# SSBDemod.net
KiCad netlist of a schematic drawn in Altium Designer
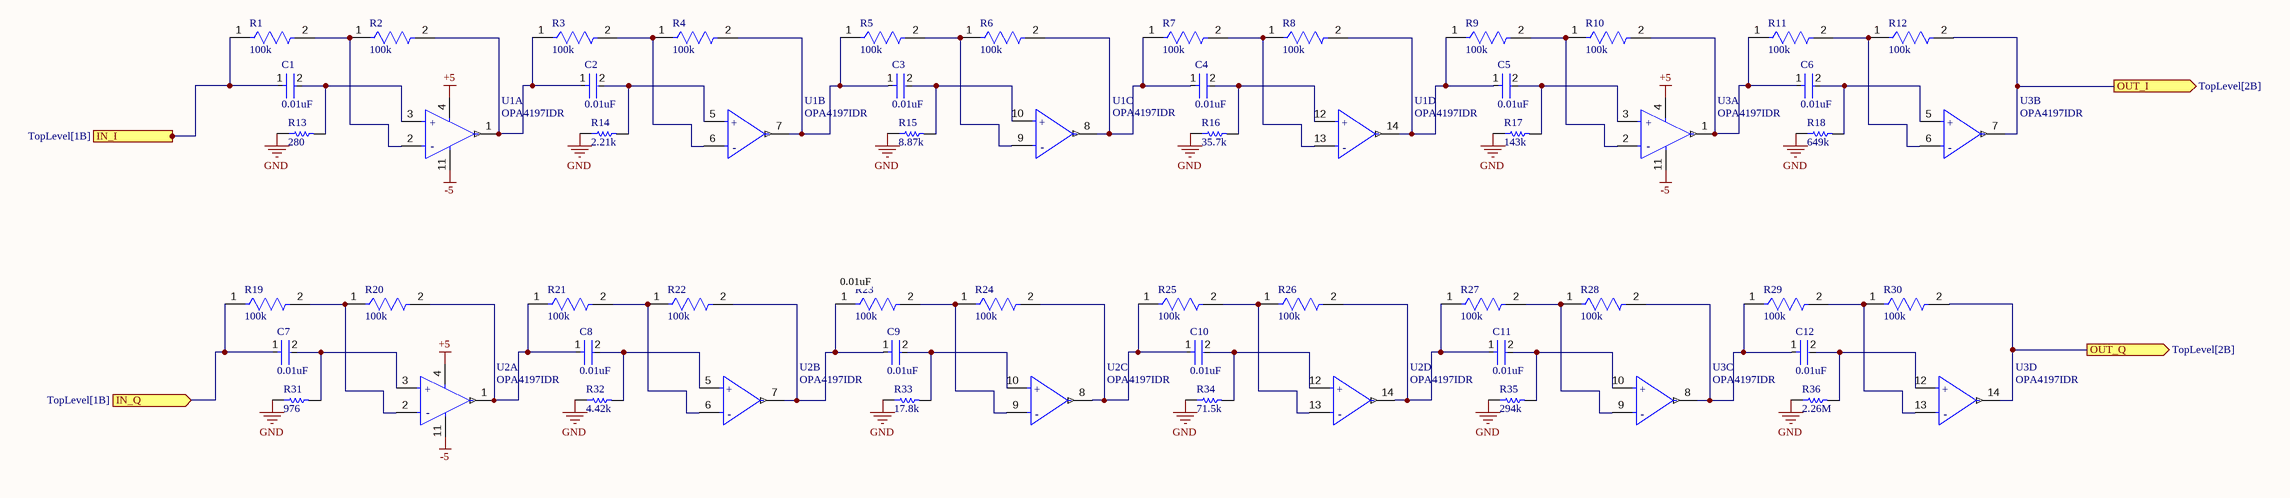
[diagram p0: SSBDemod.SchDoc]

(export (version "E")
  (design (tool "Eeschema 10.0.6"))
  (components
    (comp (ref "C1")
      (value "0.01uF")
      (footprint "FP-C0603C-CF-MFG")
      (description "CAP CER 10000PF 25V 1% NP0 0603")
      (fields
        (field (name "MANUFACTURER") "KEMET")
        (field (name "OCTOPART") "https://octopart.com/c0603c103f3gactu-kemet-12577573")
      )
      (libsource (lib "Altium Content Vault") (part "b4654b650e69147ec39a6b967a45e02"))
    )
    (comp (ref "C2")
      (value "0.01uF")
      (footprint "FP-C0603C-CF-MFG")
      (description "CAP CER 10000PF 25V 1% NP0 0603")
      (fields
        (field (name "MANUFACTURER") "KEMET")
        (field (name "OCTOPART") "https://octopart.com/c0603c103f3gactu-kemet-12577573")
      )
      (libsource (lib "Altium Content Vault") (part "b4654b650e69147ec39a6b967a45e02"))
    )
    (comp (ref "C3")
      (value "0.01uF")
      (footprint "FP-C0603C-CF-MFG")
      (description "CAP CER 10000PF 25V 1% NP0 0603")
      (fields
        (field (name "MANUFACTURER") "KEMET")
        (field (name "OCTOPART") "https://octopart.com/c0603c103f3gactu-kemet-12577573")
      )
      (libsource (lib "Altium Content Vault") (part "b4654b650e69147ec39a6b967a45e02"))
    )
    (comp (ref "C4")
      (value "0.01uF")
      (footprint "FP-C0603C-CF-MFG")
      (description "CAP CER 10000PF 25V 1% NP0 0603")
      (fields
        (field (name "MANUFACTURER") "KEMET")
        (field (name "OCTOPART") "https://octopart.com/c0603c103f3gactu-kemet-12577573")
      )
      (libsource (lib "Altium Content Vault") (part "b4654b650e69147ec39a6b967a45e02"))
    )
    (comp (ref "C5")
      (value "0.01uF")
      (footprint "FP-C0603C-CF-MFG")
      (description "CAP CER 10000PF 25V 1% NP0 0603")
      (fields
        (field (name "MANUFACTURER") "KEMET")
        (field (name "OCTOPART") "https://octopart.com/c0603c103f3gactu-kemet-12577573")
      )
      (libsource (lib "Altium Content Vault") (part "b4654b650e69147ec39a6b967a45e02"))
    )
    (comp (ref "C6")
      (value "0.01uF")
      (footprint "FP-C0603C-CF-MFG")
      (description "CAP CER 10000PF 25V 1% NP0 0603")
      (fields
        (field (name "MANUFACTURER") "KEMET")
        (field (name "OCTOPART") "https://octopart.com/c0603c103f3gactu-kemet-12577573")
      )
      (libsource (lib "Altium Content Vault") (part "b4654b650e69147ec39a6b967a45e02"))
    )
    (comp (ref "C7")
      (value "0.01uF")
      (footprint "FP-C0603C-CF-MFG")
      (description "CAP CER 10000PF 25V 1% NP0 0603")
      (fields
        (field (name "MANUFACTURER") "KEMET")
        (field (name "OCTOPART") "https://octopart.com/c0603c103f3gactu-kemet-12577573")
      )
      (libsource (lib "Altium Content Vault") (part "b4654b650e69147ec39a6b967a45e02"))
    )
    (comp (ref "C8")
      (value "0.01uF")
      (footprint "FP-C0603C-CF-MFG")
      (description "CAP CER 10000PF 25V 1% NP0 0603")
      (fields
        (field (name "MANUFACTURER") "KEMET")
        (field (name "OCTOPART") "https://octopart.com/c0603c103f3gactu-kemet-12577573")
      )
      (libsource (lib "Altium Content Vault") (part "b4654b650e69147ec39a6b967a45e02"))
    )
    (comp (ref "C9")
      (value "0.01uF")
      (footprint "FP-C0603C-CF-MFG")
      (description "CAP CER 10000PF 25V 1% NP0 0603")
      (fields
        (field (name "MANUFACTURER") "KEMET")
        (field (name "OCTOPART") "https://octopart.com/c0603c103f3gactu-kemet-12577573")
      )
      (libsource (lib "Altium Content Vault") (part "b4654b650e69147ec39a6b967a45e02"))
    )
    (comp (ref "C10")
      (value "0.01uF")
      (footprint "FP-C0603C-CF-MFG")
      (description "CAP CER 10000PF 25V 1% NP0 0603")
      (fields
        (field (name "MANUFACTURER") "KEMET")
        (field (name "OCTOPART") "https://octopart.com/c0603c103f3gactu-kemet-12577573")
      )
      (libsource (lib "Altium Content Vault") (part "b4654b650e69147ec39a6b967a45e02"))
    )
    (comp (ref "C11")
      (value "0.01uF")
      (footprint "FP-C0603C-CF-MFG")
      (description "CAP CER 10000PF 25V 1% NP0 0603")
      (fields
        (field (name "MANUFACTURER") "KEMET")
        (field (name "OCTOPART") "https://octopart.com/c0603c103f3gactu-kemet-12577573")
      )
      (libsource (lib "Altium Content Vault") (part "b4654b650e69147ec39a6b967a45e02"))
    )
    (comp (ref "C12")
      (value "0.01uF")
      (footprint "FP-C0603C-CF-MFG")
      (description "CAP CER 10000PF 25V 1% NP0 0603")
      (fields
        (field (name "MANUFACTURER") "KEMET")
        (field (name "OCTOPART") "https://octopart.com/c0603c103f3gactu-kemet-12577573")
      )
      (libsource (lib "Altium Content Vault") (part "b4654b650e69147ec39a6b967a45e02"))
    )
    (comp (ref "R1")
      (value "100k")
      (footprint "FP-RC0805-0_6-IPC_C")
      (description "RES 100K OHM 1% 1/8W 0805")
      (fields (field (name "TOLERANCE") "1%"))
      (libsource (lib "Altium Content Vault") (part "1029c3af85768c4190bb7ad29bc67b5"))
    )
    (comp (ref "R2")
      (value "100k")
      (footprint "FP-RC0805-0_6-IPC_C")
      (description "RES 100K OHM 1% 1/8W 0805")
      (fields (field (name "TOLERANCE") "1%"))
      (libsource (lib "Altium Content Vault") (part "1029c3af85768c4190bb7ad29bc67b5"))
    )
    (comp (ref "R3")
      (value "100k")
      (footprint "FP-RC0805-0_6-IPC_C")
      (description "RES 100K OHM 1% 1/8W 0805")
      (fields (field (name "TOLERANCE") "1%"))
      (libsource (lib "Altium Content Vault") (part "1029c3af85768c4190bb7ad29bc67b5"))
    )
    (comp (ref "R4")
      (value "100k")
      (footprint "FP-RC0805-0_6-IPC_C")
      (description "RES 100K OHM 1% 1/8W 0805")
      (fields (field (name "TOLERANCE") "1%"))
      (libsource (lib "Altium Content Vault") (part "1029c3af85768c4190bb7ad29bc67b5"))
    )
    (comp (ref "R5")
      (value "100k")
      (footprint "FP-RC0805-0_6-IPC_C")
      (description "RES 100K OHM 1% 1/8W 0805")
      (fields (field (name "TOLERANCE") "1%"))
      (libsource (lib "Altium Content Vault") (part "1029c3af85768c4190bb7ad29bc67b5"))
    )
    (comp (ref "R6")
      (value "100k")
      (footprint "FP-RC0805-0_6-IPC_C")
      (description "RES 100K OHM 1% 1/8W 0805")
      (fields (field (name "TOLERANCE") "1%"))
      (libsource (lib "Altium Content Vault") (part "1029c3af85768c4190bb7ad29bc67b5"))
    )
    (comp (ref "R7")
      (value "100k")
      (footprint "FP-RC0805-0_6-IPC_C")
      (description "RES 100K OHM 1% 1/8W 0805")
      (fields (field (name "TOLERANCE") "1%"))
      (libsource (lib "Altium Content Vault") (part "1029c3af85768c4190bb7ad29bc67b5"))
    )
    (comp (ref "R8")
      (value "100k")
      (footprint "FP-RC0805-0_6-IPC_C")
      (description "RES 100K OHM 1% 1/8W 0805")
      (fields (field (name "TOLERANCE") "1%"))
      (libsource (lib "Altium Content Vault") (part "1029c3af85768c4190bb7ad29bc67b5"))
    )
    (comp (ref "R9")
      (value "100k")
      (footprint "FP-RC0805-0_6-IPC_C")
      (description "RES 100K OHM 1% 1/8W 0805")
      (fields (field (name "TOLERANCE") "1%"))
      (libsource (lib "Altium Content Vault") (part "1029c3af85768c4190bb7ad29bc67b5"))
    )
    (comp (ref "R10")
      (value "100k")
      (footprint "FP-RC0805-0_6-IPC_C")
      (description "RES 100K OHM 1% 1/8W 0805")
      (fields (field (name "TOLERANCE") "1%"))
      (libsource (lib "Altium Content Vault") (part "1029c3af85768c4190bb7ad29bc67b5"))
    )
    (comp (ref "R11")
      (value "100k")
      (footprint "FP-RC0805-0_6-IPC_C")
      (description "RES 100K OHM 1% 1/8W 0805")
      (fields (field (name "TOLERANCE") "1%"))
      (libsource (lib "Altium Content Vault") (part "1029c3af85768c4190bb7ad29bc67b5"))
    )
    (comp (ref "R12")
      (value "100k")
      (footprint "FP-RC0805-0_6-IPC_C")
      (description "RES 100K OHM 1% 1/8W 0805")
      (fields (field (name "TOLERANCE") "1%"))
      (libsource (lib "Altium Content Vault") (part "1029c3af85768c4190bb7ad29bc67b5"))
    )
    (comp (ref "R13")
      (value "280")
      (footprint "RESC2013X60X35ML10T20")
      (fields (field (name "MANUFACTURER") "Yageo") (field (name "PART NUMBER") "RC0805FR-07280RL"))
      (libsource (lib "Altium Content Vault") (part "RES"))
    )
    (comp (ref "R14")
      (value "2.21k")
      (footprint "RESC2013X60X35ML10T20")
      (fields (field (name "MANUFACTURER") "Yageo") (field (name "PART NUMBER") "RC0805FR-072K21L"))
      (libsource (lib "Altium Content Vault") (part "RES"))
    )
    (comp (ref "R15")
      (value "8.87k")
      (footprint "RESC2013X60X35ML10T20")
      (fields (field (name "MANUFACTURER") "Yageo") (field (name "PART NUMBER") "RC0805FR-07280RL"))
      (libsource (lib "Altium Content Vault") (part "RES"))
    )
    (comp (ref "R16")
      (value "35.7k")
      (footprint "RESC2013X60X35ML10T20")
      (fields (field (name "MANUFACTURER") "Yageo") (field (name "PART NUMBER") "RC0805FR-07280RL"))
      (libsource (lib "Altium Content Vault") (part "RES"))
    )
    (comp (ref "R17")
      (value "143k")
      (footprint "RESC2013X60X35ML10T20")
      (fields (field (name "MANUFACTURER") "Yageo") (field (name "PART NUMBER") "RC0805FR-07280RL"))
      (libsource (lib "Altium Content Vault") (part "RES"))
    )
    (comp (ref "R18")
      (value "649k")
      (footprint "RESC2013X60X35ML10T20")
      (fields (field (name "MANUFACTURER") "Yageo") (field (name "PART NUMBER") "RC0805FR-07280RL"))
      (libsource (lib "Altium Content Vault") (part "RES"))
    )
    (comp (ref "R19")
      (value "100k")
      (footprint "FP-RC0805-0_6-IPC_C")
      (description "RES 100K OHM 1% 1/8W 0805")
      (fields (field (name "TOLERANCE") "1%"))
      (libsource (lib "Altium Content Vault") (part "1029c3af85768c4190bb7ad29bc67b5"))
    )
    (comp (ref "R20")
      (value "100k")
      (footprint "FP-RC0805-0_6-IPC_C")
      (description "RES 100K OHM 1% 1/8W 0805")
      (fields (field (name "TOLERANCE") "1%"))
      (libsource (lib "Altium Content Vault") (part "1029c3af85768c4190bb7ad29bc67b5"))
    )
    (comp (ref "R21")
      (value "100k")
      (footprint "FP-RC0805-0_6-IPC_C")
      (description "RES 100K OHM 1% 1/8W 0805")
      (fields (field (name "TOLERANCE") "1%"))
      (libsource (lib "Altium Content Vault") (part "1029c3af85768c4190bb7ad29bc67b5"))
    )
    (comp (ref "R22")
      (value "100k")
      (footprint "FP-RC0805-0_6-IPC_C")
      (description "RES 100K OHM 1% 1/8W 0805")
      (fields (field (name "TOLERANCE") "1%"))
      (libsource (lib "Altium Content Vault") (part "1029c3af85768c4190bb7ad29bc67b5"))
    )
    (comp (ref "R23")
      (value "100k")
      (footprint "FP-RC0805-0_6-IPC_C")
      (description "RES 100K OHM 1% 1/8W 0805")
      (fields (field (name "TOLERANCE") "1%"))
      (libsource (lib "Altium Content Vault") (part "1029c3af85768c4190bb7ad29bc67b5"))
    )
    (comp (ref "R24")
      (value "100k")
      (footprint "FP-RC0805-0_6-IPC_C")
      (description "RES 100K OHM 1% 1/8W 0805")
      (fields (field (name "TOLERANCE") "1%"))
      (libsource (lib "Altium Content Vault") (part "1029c3af85768c4190bb7ad29bc67b5"))
    )
    (comp (ref "R25")
      (value "100k")
      (footprint "FP-RC0805-0_6-IPC_C")
      (description "RES 100K OHM 1% 1/8W 0805")
      (fields (field (name "TOLERANCE") "1%"))
      (libsource (lib "Altium Content Vault") (part "1029c3af85768c4190bb7ad29bc67b5"))
    )
    (comp (ref "R26")
      (value "100k")
      (footprint "FP-RC0805-0_6-IPC_C")
      (description "RES 100K OHM 1% 1/8W 0805")
      (fields (field (name "TOLERANCE") "1%"))
      (libsource (lib "Altium Content Vault") (part "1029c3af85768c4190bb7ad29bc67b5"))
    )
    (comp (ref "R27")
      (value "100k")
      (footprint "FP-RC0805-0_6-IPC_C")
      (description "RES 100K OHM 1% 1/8W 0805")
      (fields (field (name "TOLERANCE") "1%"))
      (libsource (lib "Altium Content Vault") (part "1029c3af85768c4190bb7ad29bc67b5"))
    )
    (comp (ref "R28")
      (value "100k")
      (footprint "FP-RC0805-0_6-IPC_C")
      (description "RES 100K OHM 1% 1/8W 0805")
      (fields (field (name "TOLERANCE") "1%"))
      (libsource (lib "Altium Content Vault") (part "1029c3af85768c4190bb7ad29bc67b5"))
    )
    (comp (ref "R29")
      (value "100k")
      (footprint "FP-RC0805-0_6-IPC_C")
      (description "RES 100K OHM 1% 1/8W 0805")
      (fields (field (name "TOLERANCE") "1%"))
      (libsource (lib "Altium Content Vault") (part "1029c3af85768c4190bb7ad29bc67b5"))
    )
    (comp (ref "R30")
      (value "100k")
      (footprint "FP-RC0805-0_6-IPC_C")
      (description "RES 100K OHM 1% 1/8W 0805")
      (fields (field (name "TOLERANCE") "1%"))
      (libsource (lib "Altium Content Vault") (part "1029c3af85768c4190bb7ad29bc67b5"))
    )
    (comp (ref "R31")
      (value "976")
      (footprint "RESC2013X60X35ML10T20")
      (fields (field (name "MANUFACTURER") "Yageo") (field (name "PART NUMBER") "RC0805FR-07280RL"))
      (libsource (lib "Altium Content Vault") (part "RES"))
    )
    (comp (ref "R32")
      (value "4.42k")
      (footprint "RESC2013X60X35ML10T20")
      (fields (field (name "MANUFACTURER") "Yageo") (field (name "PART NUMBER") "RC0805FR-07280RL"))
      (libsource (lib "Altium Content Vault") (part "RES"))
    )
    (comp (ref "R33")
      (value "17.8k")
      (footprint "RESC2013X60X35ML10T20")
      (fields (field (name "MANUFACTURER") "Yageo") (field (name "PART NUMBER") "RC0805FR-07280RL"))
      (libsource (lib "Altium Content Vault") (part "RES"))
    )
    (comp (ref "R34")
      (value "71.5k")
      (footprint "RESC2013X60X35ML10T20")
      (fields (field (name "MANUFACTURER") "Yageo") (field (name "PART NUMBER") "RC0805FR-07280RL"))
      (libsource (lib "Altium Content Vault") (part "RES"))
    )
    (comp (ref "R35")
      (value "294k")
      (footprint "RESC2013X60X35ML10T20")
      (fields (field (name "MANUFACTURER") "Yageo") (field (name "PART NUMBER") "RC0805FR-07280RL"))
      (libsource (lib "Altium Content Vault") (part "RES"))
    )
    (comp (ref "R36")
      (value "2.26M")
      (footprint "RESC2013X60X35ML10T20")
      (fields (field (name "MANUFACTURER") "Yageo") (field (name "PART NUMBER") "RC0805FR-07280RL"))
      (libsource (lib "Altium Content Vault") (part "RES"))
    )
    (comp (ref "U1")
      (value "OPA4197IDR")
      (footprint "FP-D0014A-MFG")
      (description "IC OPAMP GP 4 CIRCUIT 14SOIC")
      (libsource (lib "Altium Content Vault") (part "684fa0f315d4229452f837ea2b10642"))
    )
    (comp (ref "U2")
      (value "OPA4197IDR")
      (footprint "FP-D0014A-MFG")
      (description "IC OPAMP GP 4 CIRCUIT 14SOIC")
      (libsource (lib "Altium Content Vault") (part "684fa0f315d4229452f837ea2b10642"))
    )
    (comp (ref "U3")
      (value "OPA4197IDR")
      (footprint "FP-D0014A-MFG")
      (description "IC OPAMP GP 4 CIRCUIT 14SOIC")
      (libsource (lib "Altium Content Vault") (part "684fa0f315d4229452f837ea2b10642"))
    )
  )
  (nets
    (net (code "1") (name "+5") (class "Default")
      (node (ref "U1") (pin "4") (pinfunction "V+_4") (pintype "power_in"))
      (node (ref "U2") (pin "4") (pinfunction "V+_4") (pintype "power_in"))
      (node (ref "U3") (pin "4") (pinfunction "V+_4") (pintype "power_in"))
    )
    (net (code "2") (name "-5") (class "Default")
      (node (ref "U1") (pin "11") (pinfunction "V-_11") (pintype "power_in"))
      (node (ref "U2") (pin "11") (pinfunction "V-_11") (pintype "power_in"))
      (node (ref "U3") (pin "11") (pinfunction "V-_11") (pintype "power_in"))
    )
    (net (code "3") (name "/IN_I") (class "Default")
      (node (ref "C1") (pin "1") (pinfunction "1_1") (pintype "passive"))
      (node (ref "R1") (pin "1") (pinfunction "1_1") (pintype "passive"))
    )
    (net (code "4") (name "/IN_Q") (class "Default")
      (node (ref "C7") (pin "1") (pinfunction "1_1") (pintype "passive"))
      (node (ref "R19") (pin "1") (pinfunction "1_1") (pintype "passive"))
    )
    (net (code "5") (name "/OUT_I") (class "Default")
      (node (ref "R12") (pin "2") (pinfunction "2_2") (pintype "passive"))
      (node (ref "U3") (pin "7") (pinfunction "OUT_B_7") (pintype "output"))
    )
    (net (code "6") (name "/OUT_Q") (class "Default")
      (node (ref "R30") (pin "2") (pinfunction "2_2") (pintype "passive"))
      (node (ref "U3") (pin "14") (pinfunction "OUT_D_14") (pintype "output"))
    )
    (net (code "7") (name "GND") (class "Default")
      (node (ref "R13") (pin "1") (pinfunction "1_1") (pintype "passive"))
      (node (ref "R14") (pin "1") (pinfunction "1_1") (pintype "passive"))
      (node (ref "R15") (pin "1") (pinfunction "1_1") (pintype "passive"))
      (node (ref "R16") (pin "1") (pinfunction "1_1") (pintype "passive"))
      (node (ref "R17") (pin "1") (pinfunction "1_1") (pintype "passive"))
      (node (ref "R18") (pin "1") (pinfunction "1_1") (pintype "passive"))
      (node (ref "R31") (pin "1") (pinfunction "1_1") (pintype "passive"))
      (node (ref "R32") (pin "1") (pinfunction "1_1") (pintype "passive"))
      (node (ref "R33") (pin "1") (pinfunction "1_1") (pintype "passive"))
      (node (ref "R34") (pin "1") (pinfunction "1_1") (pintype "passive"))
      (node (ref "R35") (pin "1") (pinfunction "1_1") (pintype "passive"))
      (node (ref "R36") (pin "1") (pinfunction "1_1") (pintype "passive"))
    )
    (net (code "8") (name "Net-(U1A-+IN_A)") (class "Default")
      (node (ref "C1") (pin "2") (pinfunction "2_2") (pintype "passive"))
      (node (ref "R13") (pin "2") (pinfunction "2_2") (pintype "passive"))
      (node (ref "U1") (pin "3") (pinfunction "+IN_A_3") (pintype "tri_state"))
    )
    (net (code "9") (name "Net-(U1A--IN_A)") (class "Default")
      (node (ref "R1") (pin "2") (pinfunction "2_2") (pintype "passive"))
      (node (ref "R2") (pin "1") (pinfunction "1_1") (pintype "passive"))
      (node (ref "U1") (pin "2") (pinfunction "-IN_A_2") (pintype "tri_state"))
    )
    (net (code "10") (name "Net-(U1A-OUT_A)") (class "Default")
      (node (ref "C2") (pin "1") (pinfunction "1_1") (pintype "passive"))
      (node (ref "R2") (pin "2") (pinfunction "2_2") (pintype "passive"))
      (node (ref "R3") (pin "1") (pinfunction "1_1") (pintype "passive"))
      (node (ref "U1") (pin "1") (pinfunction "OUT_A_1") (pintype "output"))
    )
    (net (code "11") (name "Net-(U1B-+IN_B)") (class "Default")
      (node (ref "C2") (pin "2") (pinfunction "2_2") (pintype "passive"))
      (node (ref "R14") (pin "2") (pinfunction "2_2") (pintype "passive"))
      (node (ref "U1") (pin "5") (pinfunction "+IN_B_5") (pintype "tri_state"))
    )
    (net (code "12") (name "Net-(U1B--IN_B)") (class "Default")
      (node (ref "R3") (pin "2") (pinfunction "2_2") (pintype "passive"))
      (node (ref "R4") (pin "1") (pinfunction "1_1") (pintype "passive"))
      (node (ref "U1") (pin "6") (pinfunction "-IN_B_6") (pintype "tri_state"))
    )
    (net (code "13") (name "Net-(U1B-OUT_B)") (class "Default")
      (node (ref "C3") (pin "1") (pinfunction "1_1") (pintype "passive"))
      (node (ref "R4") (pin "2") (pinfunction "2_2") (pintype "passive"))
      (node (ref "R5") (pin "1") (pinfunction "1_1") (pintype "passive"))
      (node (ref "U1") (pin "7") (pinfunction "OUT_B_7") (pintype "output"))
    )
    (net (code "14") (name "Net-(U1C-+IN_C)") (class "Default")
      (node (ref "C3") (pin "2") (pinfunction "2_2") (pintype "passive"))
      (node (ref "R15") (pin "2") (pinfunction "2_2") (pintype "passive"))
      (node (ref "U1") (pin "10") (pinfunction "+IN_C_10") (pintype "tri_state"))
    )
    (net (code "15") (name "Net-(U1C--IN_C)") (class "Default")
      (node (ref "R5") (pin "2") (pinfunction "2_2") (pintype "passive"))
      (node (ref "R6") (pin "1") (pinfunction "1_1") (pintype "passive"))
      (node (ref "U1") (pin "9") (pinfunction "-IN_C_9") (pintype "tri_state"))
    )
    (net (code "16") (name "Net-(U1C-OUT_C)") (class "Default")
      (node (ref "C4") (pin "1") (pinfunction "1_1") (pintype "passive"))
      (node (ref "R6") (pin "2") (pinfunction "2_2") (pintype "passive"))
      (node (ref "R7") (pin "1") (pinfunction "1_1") (pintype "passive"))
      (node (ref "U1") (pin "8") (pinfunction "OUT_C_8") (pintype "output"))
    )
    (net (code "17") (name "Net-(U1D-+IN_D)") (class "Default")
      (node (ref "C4") (pin "2") (pinfunction "2_2") (pintype "passive"))
      (node (ref "R16") (pin "2") (pinfunction "2_2") (pintype "passive"))
      (node (ref "U1") (pin "12") (pinfunction "+IN_D_12") (pintype "tri_state"))
    )
    (net (code "18") (name "Net-(U1D--IN_D)") (class "Default")
      (node (ref "R7") (pin "2") (pinfunction "2_2") (pintype "passive"))
      (node (ref "R8") (pin "1") (pinfunction "1_1") (pintype "passive"))
      (node (ref "U1") (pin "13") (pinfunction "-IN_D_13") (pintype "tri_state"))
    )
    (net (code "19") (name "Net-(U1D-OUT_D)") (class "Default")
      (node (ref "C5") (pin "1") (pinfunction "1_1") (pintype "passive"))
      (node (ref "R8") (pin "2") (pinfunction "2_2") (pintype "passive"))
      (node (ref "R9") (pin "1") (pinfunction "1_1") (pintype "passive"))
      (node (ref "U1") (pin "14") (pinfunction "OUT_D_14") (pintype "output"))
    )
    (net (code "20") (name "Net-(U2A-+IN_A)") (class "Default")
      (node (ref "C7") (pin "2") (pinfunction "2_2") (pintype "passive"))
      (node (ref "R31") (pin "2") (pinfunction "2_2") (pintype "passive"))
      (node (ref "U2") (pin "3") (pinfunction "+IN_A_3") (pintype "tri_state"))
    )
    (net (code "21") (name "Net-(U2A--IN_A)") (class "Default")
      (node (ref "R19") (pin "2") (pinfunction "2_2") (pintype "passive"))
      (node (ref "R20") (pin "1") (pinfunction "1_1") (pintype "passive"))
      (node (ref "U2") (pin "2") (pinfunction "-IN_A_2") (pintype "tri_state"))
    )
    (net (code "22") (name "Net-(U2A-OUT_A)") (class "Default")
      (node (ref "C8") (pin "1") (pinfunction "1_1") (pintype "passive"))
      (node (ref "R20") (pin "2") (pinfunction "2_2") (pintype "passive"))
      (node (ref "R21") (pin "1") (pinfunction "1_1") (pintype "passive"))
      (node (ref "U2") (pin "1") (pinfunction "OUT_A_1") (pintype "output"))
    )
    (net (code "23") (name "Net-(U2B-+IN_B)") (class "Default")
      (node (ref "C8") (pin "2") (pinfunction "2_2") (pintype "passive"))
      (node (ref "R32") (pin "2") (pinfunction "2_2") (pintype "passive"))
      (node (ref "U2") (pin "5") (pinfunction "+IN_B_5") (pintype "tri_state"))
    )
    (net (code "24") (name "Net-(U2B--IN_B)") (class "Default")
      (node (ref "R21") (pin "2") (pinfunction "2_2") (pintype "passive"))
      (node (ref "R22") (pin "1") (pinfunction "1_1") (pintype "passive"))
      (node (ref "U2") (pin "6") (pinfunction "-IN_B_6") (pintype "tri_state"))
    )
    (net (code "25") (name "Net-(U2B-OUT_B)") (class "Default")
      (node (ref "C9") (pin "1") (pinfunction "1_1") (pintype "passive"))
      (node (ref "R22") (pin "2") (pinfunction "2_2") (pintype "passive"))
      (node (ref "R23") (pin "1") (pinfunction "1_1") (pintype "passive"))
      (node (ref "U2") (pin "7") (pinfunction "OUT_B_7") (pintype "output"))
    )
    (net (code "26") (name "Net-(U2C-+IN_C)") (class "Default")
      (node (ref "C9") (pin "2") (pinfunction "2_2") (pintype "passive"))
      (node (ref "R33") (pin "2") (pinfunction "2_2") (pintype "passive"))
      (node (ref "U2") (pin "10") (pinfunction "+IN_C_10") (pintype "tri_state"))
    )
    (net (code "27") (name "Net-(U2C--IN_C)") (class "Default")
      (node (ref "R23") (pin "2") (pinfunction "2_2") (pintype "passive"))
      (node (ref "R24") (pin "1") (pinfunction "1_1") (pintype "passive"))
      (node (ref "U2") (pin "9") (pinfunction "-IN_C_9") (pintype "tri_state"))
    )
    (net (code "28") (name "Net-(U2C-OUT_C)") (class "Default")
      (node (ref "C10") (pin "1") (pinfunction "1_1") (pintype "passive"))
      (node (ref "R24") (pin "2") (pinfunction "2_2") (pintype "passive"))
      (node (ref "R25") (pin "1") (pinfunction "1_1") (pintype "passive"))
      (node (ref "U2") (pin "8") (pinfunction "OUT_C_8") (pintype "output"))
    )
    (net (code "29") (name "Net-(U2D-+IN_D)") (class "Default")
      (node (ref "C10") (pin "2") (pinfunction "2_2") (pintype "passive"))
      (node (ref "R34") (pin "2") (pinfunction "2_2") (pintype "passive"))
      (node (ref "U2") (pin "12") (pinfunction "+IN_D_12") (pintype "tri_state"))
    )
    (net (code "30") (name "Net-(U2D--IN_D)") (class "Default")
      (node (ref "R25") (pin "2") (pinfunction "2_2") (pintype "passive"))
      (node (ref "R26") (pin "1") (pinfunction "1_1") (pintype "passive"))
      (node (ref "U2") (pin "13") (pinfunction "-IN_D_13") (pintype "tri_state"))
    )
    (net (code "31") (name "Net-(U2D-OUT_D)") (class "Default")
      (node (ref "C11") (pin "1") (pinfunction "1_1") (pintype "passive"))
      (node (ref "R26") (pin "2") (pinfunction "2_2") (pintype "passive"))
      (node (ref "R27") (pin "1") (pinfunction "1_1") (pintype "passive"))
      (node (ref "U2") (pin "14") (pinfunction "OUT_D_14") (pintype "output"))
    )
    (net (code "32") (name "Net-(U3A-+IN_A)") (class "Default")
      (node (ref "C5") (pin "2") (pinfunction "2_2") (pintype "passive"))
      (node (ref "R17") (pin "2") (pinfunction "2_2") (pintype "passive"))
      (node (ref "U3") (pin "3") (pinfunction "+IN_A_3") (pintype "tri_state"))
    )
    (net (code "33") (name "Net-(U3A--IN_A)") (class "Default")
      (node (ref "R10") (pin "1") (pinfunction "1_1") (pintype "passive"))
      (node (ref "R9") (pin "2") (pinfunction "2_2") (pintype "passive"))
      (node (ref "U3") (pin "2") (pinfunction "-IN_A_2") (pintype "tri_state"))
    )
    (net (code "34") (name "Net-(U3A-OUT_A)") (class "Default")
      (node (ref "C6") (pin "1") (pinfunction "1_1") (pintype "passive"))
      (node (ref "R10") (pin "2") (pinfunction "2_2") (pintype "passive"))
      (node (ref "R11") (pin "1") (pinfunction "1_1") (pintype "passive"))
      (node (ref "U3") (pin "1") (pinfunction "OUT_A_1") (pintype "output"))
    )
    (net (code "35") (name "Net-(U3B-+IN_B)") (class "Default")
      (node (ref "C6") (pin "2") (pinfunction "2_2") (pintype "passive"))
      (node (ref "R18") (pin "2") (pinfunction "2_2") (pintype "passive"))
      (node (ref "U3") (pin "5") (pinfunction "+IN_B_5") (pintype "tri_state"))
    )
    (net (code "36") (name "Net-(U3B--IN_B)") (class "Default")
      (node (ref "R11") (pin "2") (pinfunction "2_2") (pintype "passive"))
      (node (ref "R12") (pin "1") (pinfunction "1_1") (pintype "passive"))
      (node (ref "U3") (pin "6") (pinfunction "-IN_B_6") (pintype "tri_state"))
    )
    (net (code "37") (name "Net-(U3C-+IN_C)") (class "Default")
      (node (ref "C11") (pin "2") (pinfunction "2_2") (pintype "passive"))
      (node (ref "R35") (pin "2") (pinfunction "2_2") (pintype "passive"))
      (node (ref "U3") (pin "10") (pinfunction "+IN_C_10") (pintype "tri_state"))
    )
    (net (code "38") (name "Net-(U3C--IN_C)") (class "Default")
      (node (ref "R27") (pin "2") (pinfunction "2_2") (pintype "passive"))
      (node (ref "R28") (pin "1") (pinfunction "1_1") (pintype "passive"))
      (node (ref "U3") (pin "9") (pinfunction "-IN_C_9") (pintype "tri_state"))
    )
    (net (code "39") (name "Net-(U3C-OUT_C)") (class "Default")
      (node (ref "C12") (pin "1") (pinfunction "1_1") (pintype "passive"))
      (node (ref "R28") (pin "2") (pinfunction "2_2") (pintype "passive"))
      (node (ref "R29") (pin "1") (pinfunction "1_1") (pintype "passive"))
      (node (ref "U3") (pin "8") (pinfunction "OUT_C_8") (pintype "output"))
    )
    (net (code "40") (name "Net-(U3D-+IN_D)") (class "Default")
      (node (ref "C12") (pin "2") (pinfunction "2_2") (pintype "passive"))
      (node (ref "R36") (pin "2") (pinfunction "2_2") (pintype "passive"))
      (node (ref "U3") (pin "12") (pinfunction "+IN_D_12") (pintype "tri_state"))
    )
    (net (code "41") (name "Net-(U3D--IN_D)") (class "Default")
      (node (ref "R29") (pin "2") (pinfunction "2_2") (pintype "passive"))
      (node (ref "R30") (pin "1") (pinfunction "1_1") (pintype "passive"))
      (node (ref "U3") (pin "13") (pinfunction "-IN_D_13") (pintype "tri_state"))
    )
  )
)
